# HV_PWR_STAGE_6W.net
KiCad netlist of a schematic drawn in Altium Designer
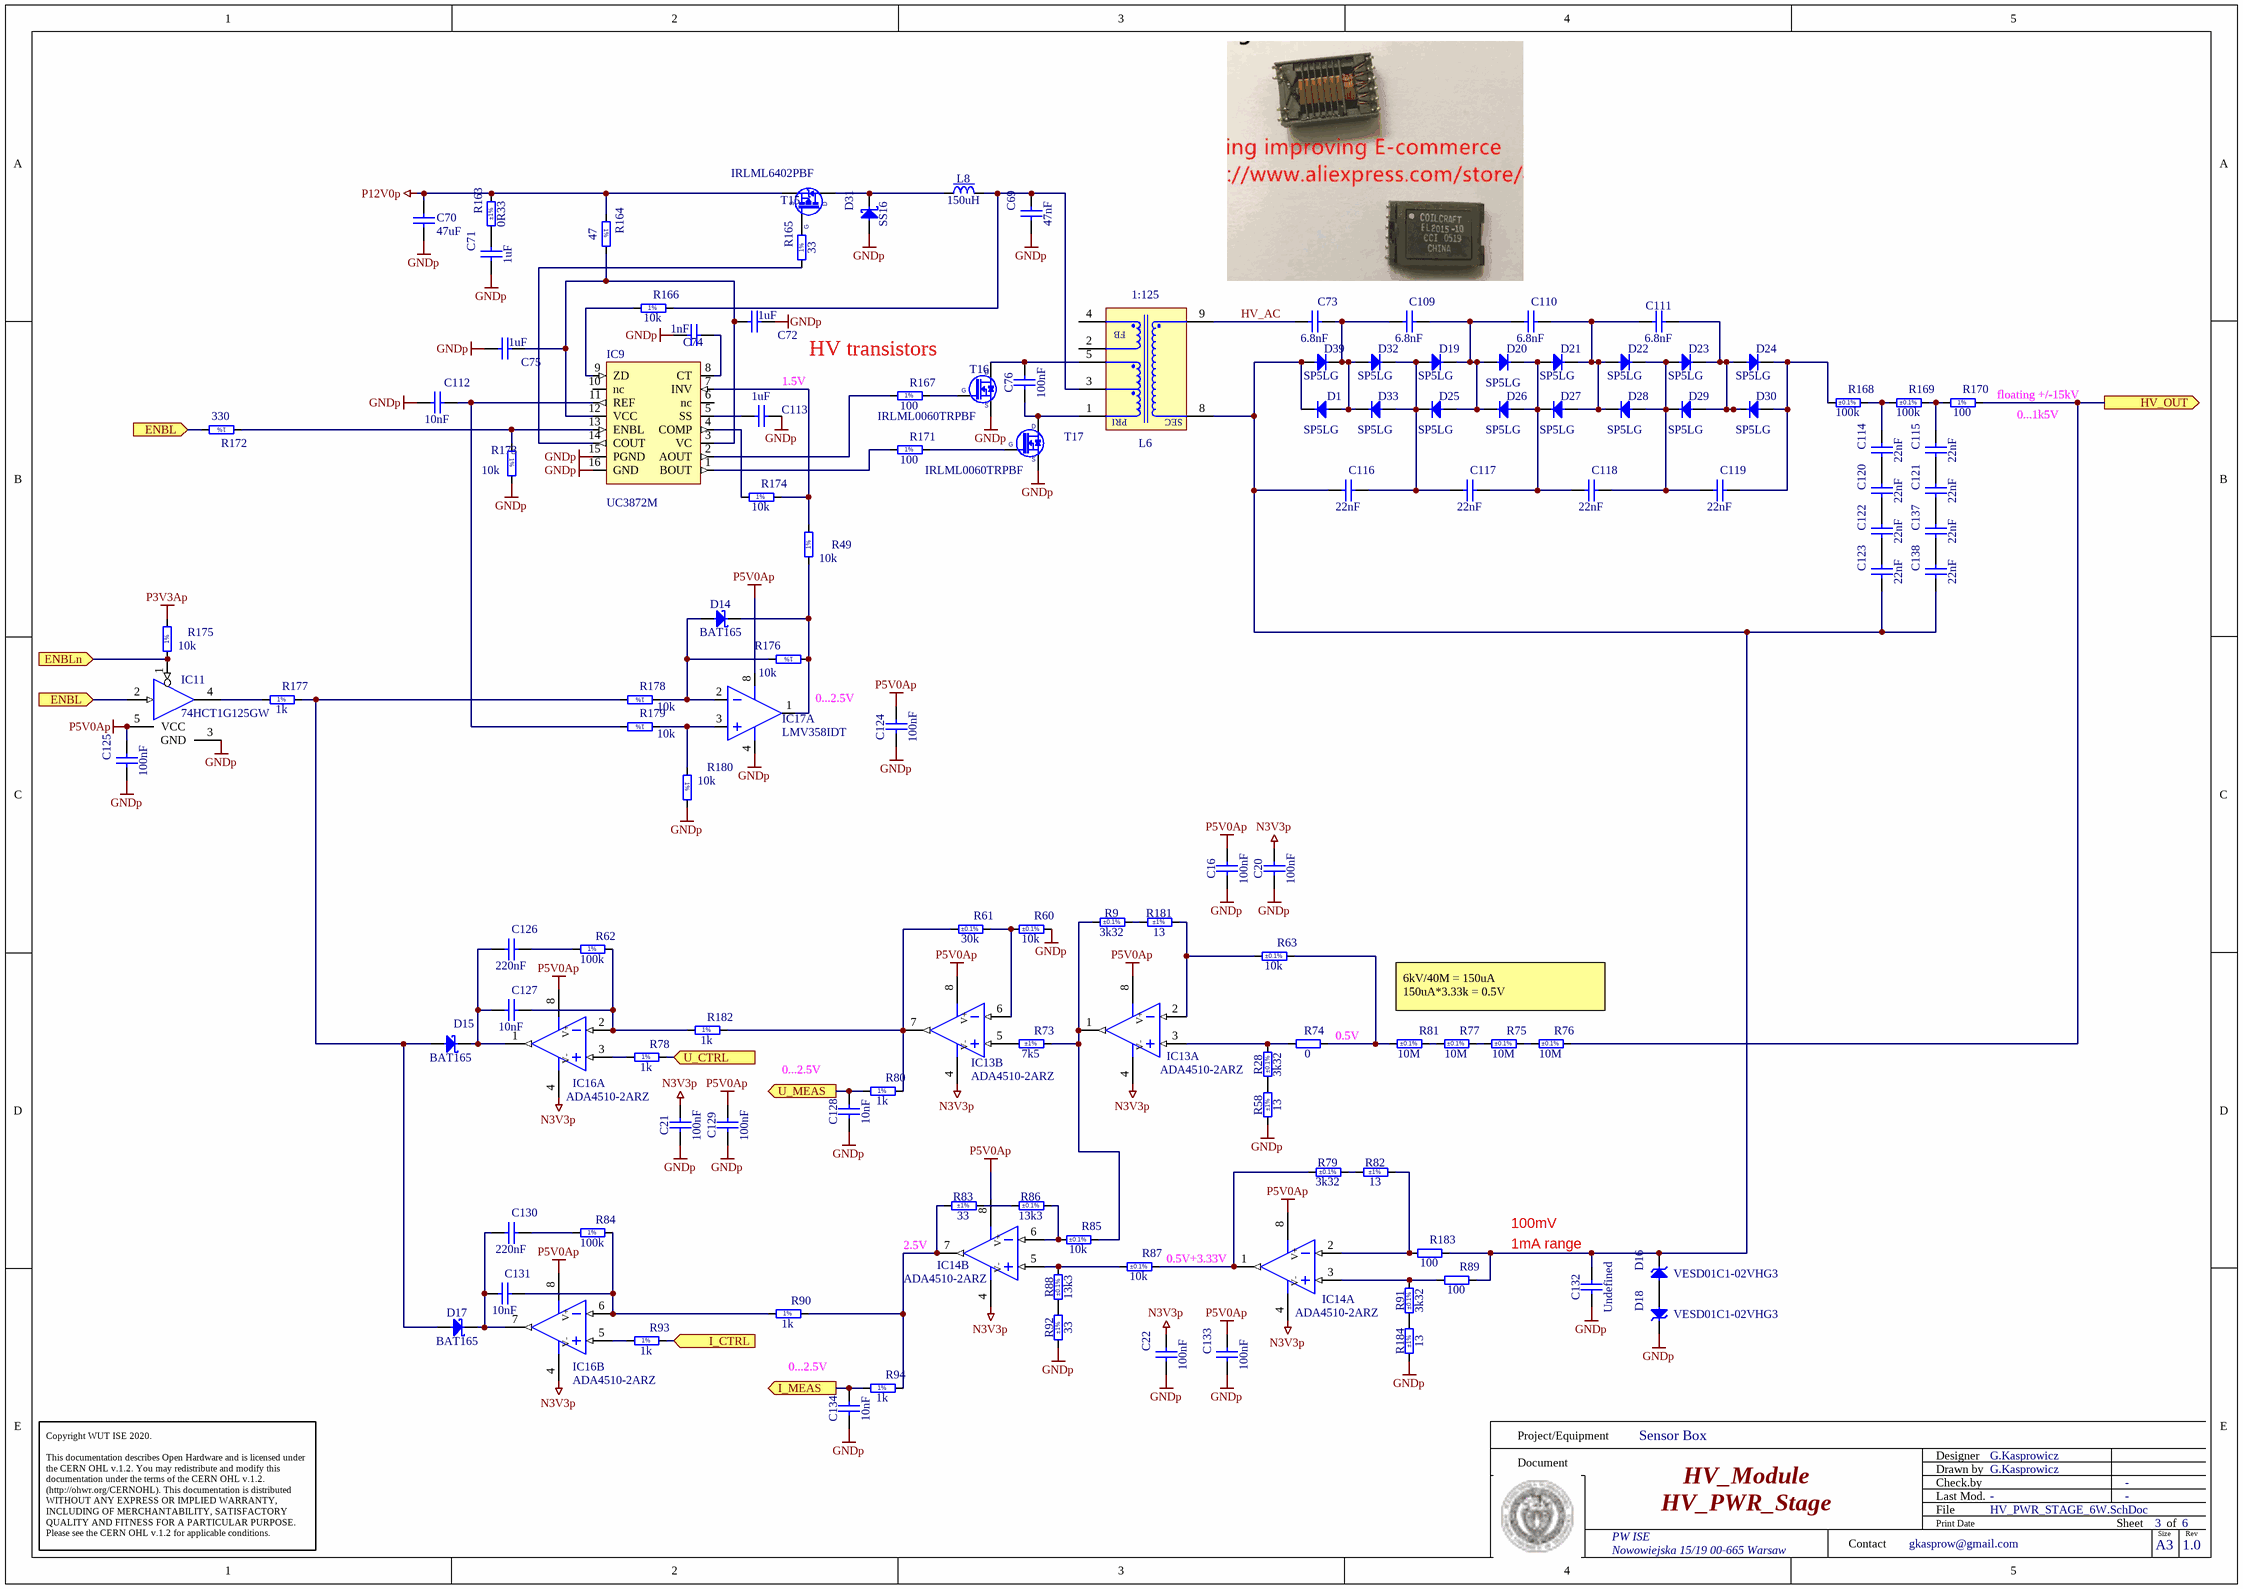
[diagram p0: HV_PWR_STAGE_6W.SchDoc]

(export (version "E")
  (design (tool "Eeschema 10.0.6"))
  (components
    (comp (ref "C16")
      (value "100nF")
      (footprint "CAPC1005X55N")
      (description "Non-polarised capacitor")
      (fields
        (field (name "PART NUMBER") "CC0402_100NF_16V_10%_X7R")
        (field (name "VOLTAGE") "16V")
        (field (name "AUTHOR") "CERN DEM JLC")
      )
      (libsource (lib "Capacitors") (part "Capacitor - non polarized"))
    )
    (comp (ref "C20")
      (value "100nF")
      (footprint "CAPC1005X55N")
      (description "Non-polarised capacitor")
      (fields
        (field (name "PART NUMBER") "CC0402_100NF_16V_10%_X7R")
        (field (name "VOLTAGE") "16V")
        (field (name "AUTHOR") "CERN DEM JLC")
      )
      (libsource (lib "Capacitors") (part "Capacitor - non polarized"))
    )
    (comp (ref "C21")
      (value "100nF")
      (footprint "CAPC1005X55N")
      (description "Non-polarised capacitor")
      (fields
        (field (name "PART NUMBER") "CC0402_100NF_16V_10%_X7R")
        (field (name "VOLTAGE") "16V")
        (field (name "AUTHOR") "CERN DEM JLC")
      )
      (libsource (lib "Capacitors") (part "Capacitor - non polarized"))
    )
    (comp (ref "C22")
      (value "100nF")
      (footprint "CAPC1005X55N")
      (description "Non-polarised capacitor")
      (fields
        (field (name "PART NUMBER") "CC0402_100NF_16V_10%_X7R")
        (field (name "VOLTAGE") "16V")
        (field (name "AUTHOR") "CERN DEM JLC")
      )
      (libsource (lib "Capacitors") (part "Capacitor - non polarized"))
    )
    (comp (ref "C69")
      (value "47nF")
      (footprint "CAPR500-250X720X650")
      (description "Non-polarised capacitor")
      (fields
        (field (name "PART NUMBER") "CPER_47NF_63V_10%_500-250X720X650")
        (field (name "VOLTAGE") "63VDC/40VAC")
        (field (name "AUTHOR") "CERN DEM JLC")
      )
      (libsource (lib "Capacitors") (part "Capacitor - non polarized"))
    )
    (comp (ref "C70")
      (value "47uF")
      (footprint "CAPC3216X180N")
      (description "Non-polarised capacitor")
      (fields
        (field (name "PART NUMBER") "CC1206_47UF_25V_20%_X5R")
        (field (name "VOLTAGE") "25V")
        (field (name "AUTHOR") "CERN DEM JLC")
      )
      (libsource (lib "Capacitors") (part "Capacitor - non polarized"))
    )
    (comp (ref "C71")
      (value "1uF")
      (footprint "CAPC1608X87N")
      (description "Non-polarised capacitor")
      (fields
        (field (name "PART NUMBER") "CC0603_1UF_25V_10%_X7R")
        (field (name "VOLTAGE") "25V")
        (field (name "AUTHOR") "CERN DEM JLC")
      )
      (libsource (lib "Capacitors") (part "Capacitor - non polarized"))
    )
    (comp (ref "C72")
      (value "1uF")
      (footprint "CAPC1608X87N")
      (description "Non-polarised capacitor")
      (fields
        (field (name "PART NUMBER") "CC0603_1UF_25V_10%_X7R")
        (field (name "VOLTAGE") "25V")
        (field (name "AUTHOR") "CERN DEM JLC")
      )
      (libsource (lib "Capacitors") (part "Capacitor - non polarized"))
    )
    (comp (ref "C73")
      (value "6.8nF")
      (footprint "CAPC3225X170N")
      (description "Non-polarised capacitor")
      (fields
        (field (name "PART NUMBER") "CC1210_6.8NF_2KV_10%_X7R")
        (field (name "VOLTAGE") "2kV")
        (field (name "AUTHOR") "GK")
      )
      (libsource (lib "Passives_RC") (part "CC1210_6.8NF_2KV_10%_X7R"))
    )
    (comp (ref "C74")
      (value "1nF")
      (footprint "CAPC1005X55N")
      (description "Non-polarised capacitor")
      (fields
        (field (name "PART NUMBER") "CC0402_1NF_50V_10%_X7R")
        (field (name "VOLTAGE") "50V")
        (field (name "AUTHOR") "CERN DEM JLC")
      )
      (libsource (lib "Capacitors") (part "Capacitor - non polarized"))
    )
    (comp (ref "C75")
      (value "1uF")
      (footprint "CAPC1608X87N")
      (description "Non-polarised capacitor")
      (fields
        (field (name "PART NUMBER") "CC0603_1UF_25V_10%_X7R")
        (field (name "VOLTAGE") "25V")
        (field (name "AUTHOR") "CERN DEM JLC")
      )
      (libsource (lib "Capacitors") (part "Capacitor - non polarized"))
    )
    (comp (ref "C76")
      (value "100nF")
      (footprint "CAPR500-250X720X650")
      (description "Non-polarised capacitor")
      (fields
        (field (name "PART NUMBER") "CPER_100NF_100V_10%_500-250X720X650")
        (field (name "VOLTAGE") "100VDC/63VAC")
        (field (name "AUTHOR") "CERN DEM JLC")
      )
      (libsource (lib "Capacitors") (part "Capacitor - non polarized"))
    )
    (comp (ref "C109")
      (value "6.8nF")
      (footprint "CAPC3225X170N")
      (description "Non-polarised capacitor")
      (fields
        (field (name "PART NUMBER") "CC1210_6.8NF_2KV_10%_X7R")
        (field (name "VOLTAGE") "2kV")
        (field (name "AUTHOR") "GK")
      )
      (libsource (lib "Passives_RC") (part "CC1210_6.8NF_2KV_10%_X7R"))
    )
    (comp (ref "C110")
      (value "6.8nF")
      (footprint "CAPC3225X170N")
      (description "Non-polarised capacitor")
      (fields
        (field (name "PART NUMBER") "CC1210_6.8NF_2KV_10%_X7R")
        (field (name "VOLTAGE") "2kV")
        (field (name "AUTHOR") "GK")
      )
      (libsource (lib "Passives_RC") (part "CC1210_6.8NF_2KV_10%_X7R"))
    )
    (comp (ref "C111")
      (value "6.8nF")
      (footprint "CAPC3225X170N")
      (description "Non-polarised capacitor")
      (fields
        (field (name "PART NUMBER") "CC1210_6.8NF_2KV_10%_X7R")
        (field (name "VOLTAGE") "2kV")
        (field (name "AUTHOR") "GK")
      )
      (libsource (lib "Passives_RC") (part "CC1210_6.8NF_2KV_10%_X7R"))
    )
    (comp (ref "C112")
      (value "10nF")
      (footprint "CAPC1608X87N")
      (description "Non-polarised capacitor")
      (fields
        (field (name "PART NUMBER") "CC0603_10NF_50V_5%_C0G")
        (field (name "VOLTAGE") "50V")
        (field (name "AUTHOR") "CERN DEM JLC")
      )
      (libsource (lib "Capacitors") (part "Capacitor - non polarized"))
    )
    (comp (ref "C113")
      (value "1uF")
      (footprint "CAPC1608X87N")
      (description "Non-polarised capacitor")
      (fields
        (field (name "PART NUMBER") "CC0603_1UF_25V_10%_X7R")
        (field (name "VOLTAGE") "25V")
        (field (name "AUTHOR") "CERN DEM JLC")
      )
      (libsource (lib "Capacitors") (part "Capacitor - non polarized"))
    )
    (comp (ref "C114")
      (value "22nF")
      (footprint "CAPC5750X330N")
      (description "Non-polarised capacitor")
      (fields
        (field (name "PART NUMBER") "CC2220_22NF_2KV_10%_X7R")
        (field (name "VOLTAGE") "2KV")
        (field (name "AUTHOR") "GK")
      )
      (libsource (lib "Passives_RC") (part "CC2220_22NF_2KV_10%_X7R"))
    )
    (comp (ref "C115")
      (value "22nF")
      (footprint "CAPC5750X330N")
      (description "Non-polarised capacitor")
      (fields
        (field (name "PART NUMBER") "CC2220_22NF_2KV_10%_X7R")
        (field (name "VOLTAGE") "2KV")
        (field (name "AUTHOR") "GK")
      )
      (libsource (lib "Passives_RC") (part "CC2220_22NF_2KV_10%_X7R"))
    )
    (comp (ref "C116")
      (value "22nF")
      (footprint "CAPC5750X330N")
      (description "Non-polarised capacitor")
      (fields
        (field (name "PART NUMBER") "CC2220_22NF_2KV_10%_X7R")
        (field (name "VOLTAGE") "2KV")
        (field (name "AUTHOR") "GK")
      )
      (libsource (lib "Passives_RC") (part "CC2220_22NF_2KV_10%_X7R"))
    )
    (comp (ref "C117")
      (value "22nF")
      (footprint "CAPC5750X330N")
      (description "Non-polarised capacitor")
      (fields
        (field (name "PART NUMBER") "CC2220_22NF_2KV_10%_X7R")
        (field (name "VOLTAGE") "2KV")
        (field (name "AUTHOR") "GK")
      )
      (libsource (lib "Passives_RC") (part "CC2220_22NF_2KV_10%_X7R"))
    )
    (comp (ref "C118")
      (value "22nF")
      (footprint "CAPC5750X330N")
      (description "Non-polarised capacitor")
      (fields
        (field (name "PART NUMBER") "CC2220_22NF_2KV_10%_X7R")
        (field (name "VOLTAGE") "2KV")
        (field (name "AUTHOR") "GK")
      )
      (libsource (lib "Passives_RC") (part "CC2220_22NF_2KV_10%_X7R"))
    )
    (comp (ref "C119")
      (value "22nF")
      (footprint "CAPC5750X330N")
      (description "Non-polarised capacitor")
      (fields
        (field (name "PART NUMBER") "CC2220_22NF_2KV_10%_X7R")
        (field (name "VOLTAGE") "2KV")
        (field (name "AUTHOR") "GK")
      )
      (libsource (lib "Passives_RC") (part "CC2220_22NF_2KV_10%_X7R"))
    )
    (comp (ref "C120")
      (value "22nF")
      (footprint "CAPC5750X330N")
      (description "Non-polarised capacitor")
      (fields
        (field (name "PART NUMBER") "CC2220_22NF_2KV_10%_X7R")
        (field (name "VOLTAGE") "2KV")
        (field (name "AUTHOR") "GK")
      )
      (libsource (lib "Passives_RC") (part "CC2220_22NF_2KV_10%_X7R"))
    )
    (comp (ref "C121")
      (value "22nF")
      (footprint "CAPC5750X330N")
      (description "Non-polarised capacitor")
      (fields
        (field (name "PART NUMBER") "CC2220_22NF_2KV_10%_X7R")
        (field (name "VOLTAGE") "2KV")
        (field (name "AUTHOR") "GK")
      )
      (libsource (lib "Passives_RC") (part "CC2220_22NF_2KV_10%_X7R"))
    )
    (comp (ref "C122")
      (value "22nF")
      (footprint "CAPC5750X330N")
      (description "Non-polarised capacitor")
      (fields
        (field (name "PART NUMBER") "CC2220_22NF_2KV_10%_X7R")
        (field (name "VOLTAGE") "2KV")
        (field (name "AUTHOR") "GK")
      )
      (libsource (lib "Passives_RC") (part "CC2220_22NF_2KV_10%_X7R"))
    )
    (comp (ref "C123")
      (value "22nF")
      (footprint "CAPC5750X330N")
      (description "Non-polarised capacitor")
      (fields
        (field (name "PART NUMBER") "CC2220_22NF_2KV_10%_X7R")
        (field (name "VOLTAGE") "2KV")
        (field (name "AUTHOR") "GK")
      )
      (libsource (lib "Passives_RC") (part "CC2220_22NF_2KV_10%_X7R"))
    )
    (comp (ref "C124")
      (value "100nF")
      (footprint "CAPC1005X55N")
      (description "Non-polarised capacitor")
      (fields
        (field (name "PART NUMBER") "CC0402_100NF_16V_10%_X7R")
        (field (name "VOLTAGE") "16V")
        (field (name "AUTHOR") "CERN DEM JLC")
      )
      (libsource (lib "Capacitors") (part "Capacitor - non polarized"))
    )
    (comp (ref "C125")
      (value "100nF")
      (footprint "CAPC1005X55N")
      (description "Non-polarised capacitor")
      (fields
        (field (name "PART NUMBER") "CC0402_100NF_16V_10%_X7R")
        (field (name "VOLTAGE") "16V")
        (field (name "AUTHOR") "CERN DEM JLC")
      )
      (libsource (lib "Capacitors") (part "Capacitor - non polarized"))
    )
    (comp (ref "C126")
      (value "220nF")
      (footprint "CAPC1608X87N")
      (description "Non-polarised capacitor")
      (fields
        (field (name "PART NUMBER") "CC0603_220NF_10V_10%_X7R")
        (field (name "VOLTAGE") "10V")
        (field (name "AUTHOR") "CERN DEM JLC")
      )
      (libsource (lib "Capacitors") (part "Capacitor - non polarized"))
    )
    (comp (ref "C127")
      (value "10nF")
      (footprint "CAPC1608X87N")
      (description "Non-polarised capacitor")
      (fields
        (field (name "PART NUMBER") "CC0603_10NF_50V_5%_C0G")
        (field (name "VOLTAGE") "50V")
        (field (name "AUTHOR") "CERN DEM JLC")
      )
      (libsource (lib "Capacitors") (part "Capacitor - non polarized"))
    )
    (comp (ref "C128")
      (value "10nF")
      (footprint "CAPC1005X55N")
      (description "Non-polarised capacitor")
      (fields
        (field (name "PART NUMBER") "CC0402_10NF_25V_10%_X7R")
        (field (name "VOLTAGE") "25V")
        (field (name "AUTHOR") "CERN DEM JLC")
      )
      (libsource (lib "Capacitors") (part "Capacitor - non polarized"))
    )
    (comp (ref "C129")
      (value "100nF")
      (footprint "CAPC1005X55N")
      (description "Non-polarised capacitor")
      (fields
        (field (name "PART NUMBER") "CC0402_100NF_16V_10%_X7R")
        (field (name "VOLTAGE") "16V")
        (field (name "AUTHOR") "CERN DEM JLC")
      )
      (libsource (lib "Capacitors") (part "Capacitor - non polarized"))
    )
    (comp (ref "C130")
      (value "220nF")
      (footprint "CAPC1608X87N")
      (description "Non-polarised capacitor")
      (fields
        (field (name "PART NUMBER") "CC0603_220NF_10V_10%_X7R")
        (field (name "VOLTAGE") "10V")
        (field (name "AUTHOR") "CERN DEM JLC")
      )
      (libsource (lib "Capacitors") (part "Capacitor - non polarized"))
    )
    (comp (ref "C131")
      (value "10nF")
      (footprint "CAPC1608X87N")
      (description "Non-polarised capacitor")
      (fields
        (field (name "PART NUMBER") "CC0603_10NF_50V_5%_C0G")
        (field (name "VOLTAGE") "50V")
        (field (name "AUTHOR") "CERN DEM JLC")
      )
      (libsource (lib "Capacitors") (part "Capacitor - non polarized"))
    )
    (comp (ref "C132")
      (value "Undefined")
      (footprint "CAPC1608X90N")
      (description "Non-polarised capacitor")
      (fields (field (name "PART NUMBER") "CC0603_NO-VALUE") (field (name "AUTHOR") "CERN DEM MR"))
      (libsource (lib "Capacitors") (part "Capacitor - non polarized"))
    )
    (comp (ref "C133")
      (value "100nF")
      (footprint "CAPC1005X55N")
      (description "Non-polarised capacitor")
      (fields
        (field (name "PART NUMBER") "CC0402_100NF_16V_10%_X7R")
        (field (name "VOLTAGE") "16V")
        (field (name "AUTHOR") "CERN DEM JLC")
      )
      (libsource (lib "Capacitors") (part "Capacitor - non polarized"))
    )
    (comp (ref "C134")
      (value "10nF")
      (footprint "CAPC1005X55N")
      (description "Non-polarised capacitor")
      (fields
        (field (name "PART NUMBER") "CC0402_10NF_25V_10%_X7R")
        (field (name "VOLTAGE") "25V")
        (field (name "AUTHOR") "CERN DEM JLC")
      )
      (libsource (lib "Capacitors") (part "Capacitor - non polarized"))
    )
    (comp (ref "C137")
      (value "22nF")
      (footprint "CAPC5750X330N")
      (description "Non-polarised capacitor")
      (fields
        (field (name "PART NUMBER") "CC2220_22NF_2KV_10%_X7R")
        (field (name "VOLTAGE") "2KV")
        (field (name "AUTHOR") "GK")
      )
      (libsource (lib "Passives_RC") (part "CC2220_22NF_2KV_10%_X7R"))
    )
    (comp (ref "C138")
      (value "22nF")
      (footprint "CAPC5750X330N")
      (description "Non-polarised capacitor")
      (fields
        (field (name "PART NUMBER") "CC2220_22NF_2KV_10%_X7R")
        (field (name "VOLTAGE") "2KV")
        (field (name "AUTHOR") "GK")
      )
      (libsource (lib "Passives_RC") (part "CC2220_22NF_2KV_10%_X7R"))
    )
    (comp (ref "D1")
      (value "SP5LG")
      (footprint "DO-214AC_GW")
      (description "270mA High Voltage Fast Recovery Rectifier 5000 Volts")
      (fields (field (name "VOLTAGE") "5000V") (field (name "POWER") "270mA") (field (name "AUTHOR") "GK"))
      (libsource (lib "Diodes") (part "D_SP5LG"))
    )
    (comp (ref "D14")
      (value "BAT165")
      (footprint "SOD2512X110N")
      (description "Schottky Diode")
      (fields
        (field (name "VOLTAGE") "40V")
        (field (name "POWER") "750mA")
        (field (name "AUTHOR") "CERN DEM JLC")
      )
      (libsource (lib "ICs And Semiconductors") (part "Diode Schottky"))
    )
    (comp (ref "D15")
      (value "BAT165")
      (footprint "SOD2512X110N")
      (description "Schottky Diode")
      (fields
        (field (name "VOLTAGE") "40V")
        (field (name "POWER") "750mA")
        (field (name "AUTHOR") "CERN DEM JLC")
      )
      (libsource (lib "ICs And Semiconductors") (part "Diode Schottky"))
    )
    (comp (ref "D16")
      (value "VESD01C1-02VHG3")
      (footprint "SODFL1608X70N")
      (description "Transient Voltage Suppressor Diode (Uni-Directional)")
      (fields
        (field (name "VOLTAGE") "1V")
        (field (name "POWER") "100W")
        (field (name "AUTHOR") "CERN DEM BC")
      )
      (libsource (lib "ICs And Semiconductors") (part "Diode TVS Uni-Directional"))
    )
    (comp (ref "D17")
      (value "BAT165")
      (footprint "SOD2512X110N")
      (description "Schottky Diode")
      (fields
        (field (name "VOLTAGE") "40V")
        (field (name "POWER") "750mA")
        (field (name "AUTHOR") "CERN DEM JLC")
      )
      (libsource (lib "ICs And Semiconductors") (part "Diode Schottky"))
    )
    (comp (ref "D18")
      (value "VESD01C1-02VHG3")
      (footprint "SODFL1608X70N")
      (description "Transient Voltage Suppressor Diode (Uni-Directional)")
      (fields
        (field (name "VOLTAGE") "1V")
        (field (name "POWER") "100W")
        (field (name "AUTHOR") "CERN DEM BC")
      )
      (libsource (lib "ICs And Semiconductors") (part "Diode TVS Uni-Directional"))
    )
    (comp (ref "D19")
      (value "SP5LG")
      (footprint "DO-214AC_GW")
      (description "270mA High Voltage Fast Recovery Rectifier 5000 Volts")
      (fields (field (name "VOLTAGE") "5000V") (field (name "POWER") "270mA") (field (name "AUTHOR") "GK"))
      (libsource (lib "Diodes") (part "D_SP5LG"))
    )
    (comp (ref "D20")
      (value "SP5LG")
      (footprint "DO-214AC_GW")
      (description "270mA High Voltage Fast Recovery Rectifier 5000 Volts")
      (fields (field (name "VOLTAGE") "5000V") (field (name "POWER") "270mA") (field (name "AUTHOR") "GK"))
      (libsource (lib "Diodes") (part "D_SP5LG"))
    )
    (comp (ref "D21")
      (value "SP5LG")
      (footprint "DO-214AC_GW")
      (description "270mA High Voltage Fast Recovery Rectifier 5000 Volts")
      (fields (field (name "VOLTAGE") "5000V") (field (name "POWER") "270mA") (field (name "AUTHOR") "GK"))
      (libsource (lib "Diodes") (part "D_SP5LG"))
    )
    (comp (ref "D22")
      (value "SP5LG")
      (footprint "DO-214AC_GW")
      (description "270mA High Voltage Fast Recovery Rectifier 5000 Volts")
      (fields (field (name "VOLTAGE") "5000V") (field (name "POWER") "270mA") (field (name "AUTHOR") "GK"))
      (libsource (lib "Diodes") (part "D_SP5LG"))
    )
    (comp (ref "D23")
      (value "SP5LG")
      (footprint "DO-214AC_GW")
      (description "270mA High Voltage Fast Recovery Rectifier 5000 Volts")
      (fields (field (name "VOLTAGE") "5000V") (field (name "POWER") "270mA") (field (name "AUTHOR") "GK"))
      (libsource (lib "Diodes") (part "D_SP5LG"))
    )
    (comp (ref "D24")
      (value "SP5LG")
      (footprint "DO-214AC_GW")
      (description "270mA High Voltage Fast Recovery Rectifier 5000 Volts")
      (fields (field (name "VOLTAGE") "5000V") (field (name "POWER") "270mA") (field (name "AUTHOR") "GK"))
      (libsource (lib "Diodes") (part "D_SP5LG"))
    )
    (comp (ref "D25")
      (value "SP5LG")
      (footprint "DO-214AC_GW")
      (description "270mA High Voltage Fast Recovery Rectifier 5000 Volts")
      (fields (field (name "VOLTAGE") "5000V") (field (name "POWER") "270mA") (field (name "AUTHOR") "GK"))
      (libsource (lib "Diodes") (part "D_SP5LG"))
    )
    (comp (ref "D26")
      (value "SP5LG")
      (footprint "DO-214AC_GW")
      (description "270mA High Voltage Fast Recovery Rectifier 5000 Volts")
      (fields (field (name "VOLTAGE") "5000V") (field (name "POWER") "270mA") (field (name "AUTHOR") "GK"))
      (libsource (lib "Diodes") (part "D_SP5LG"))
    )
    (comp (ref "D27")
      (value "SP5LG")
      (footprint "DO-214AC_GW")
      (description "270mA High Voltage Fast Recovery Rectifier 5000 Volts")
      (fields (field (name "VOLTAGE") "5000V") (field (name "POWER") "270mA") (field (name "AUTHOR") "GK"))
      (libsource (lib "Diodes") (part "D_SP5LG"))
    )
    (comp (ref "D28")
      (value "SP5LG")
      (footprint "DO-214AC_GW")
      (description "270mA High Voltage Fast Recovery Rectifier 5000 Volts")
      (fields (field (name "VOLTAGE") "5000V") (field (name "POWER") "270mA") (field (name "AUTHOR") "GK"))
      (libsource (lib "Diodes") (part "D_SP5LG"))
    )
    (comp (ref "D29")
      (value "SP5LG")
      (footprint "DO-214AC_GW")
      (description "270mA High Voltage Fast Recovery Rectifier 5000 Volts")
      (fields (field (name "VOLTAGE") "5000V") (field (name "POWER") "270mA") (field (name "AUTHOR") "GK"))
      (libsource (lib "Diodes") (part "D_SP5LG"))
    )
    (comp (ref "D30")
      (value "SP5LG")
      (footprint "DO-214AC_GW")
      (description "270mA High Voltage Fast Recovery Rectifier 5000 Volts")
      (fields (field (name "VOLTAGE") "5000V") (field (name "POWER") "270mA") (field (name "AUTHOR") "GK"))
      (libsource (lib "Diodes") (part "D_SP5LG"))
    )
    (comp (ref "D31")
      (value "SS16")
      (footprint "DIOM5127X229N")
      (description "Schottky Diode")
      (fields
        (field (name "VOLTAGE") "60V")
        (field (name "POWER") "1A")
        (field (name "AUTHOR") "CERN DEM JLC")
      )
      (libsource (lib "ICs And Semiconductors") (part "Diode Schottky"))
    )
    (comp (ref "D32")
      (value "SP5LG")
      (footprint "DO-214AC_GW")
      (description "270mA High Voltage Fast Recovery Rectifier 5000 Volts")
      (fields (field (name "VOLTAGE") "5000V") (field (name "POWER") "270mA") (field (name "AUTHOR") "GK"))
      (libsource (lib "Diodes") (part "D_SP5LG"))
    )
    (comp (ref "D33")
      (value "SP5LG")
      (footprint "DO-214AC_GW")
      (description "270mA High Voltage Fast Recovery Rectifier 5000 Volts")
      (fields (field (name "VOLTAGE") "5000V") (field (name "POWER") "270mA") (field (name "AUTHOR") "GK"))
      (libsource (lib "Diodes") (part "D_SP5LG"))
    )
    (comp (ref "D39")
      (value "SP5LG")
      (footprint "DO-214AC_GW")
      (description "270mA High Voltage Fast Recovery Rectifier 5000 Volts")
      (fields (field (name "VOLTAGE") "5000V") (field (name "POWER") "270mA") (field (name "AUTHOR") "GK"))
      (libsource (lib "Diodes") (part "D_SP5LG"))
    )
    (comp (ref "IC9")
      (value "UC3872M")
      (footprint "R-PDSO-G16")
      (description "Resonant Lamp Ballast Controller")
      (libsource (lib "LIBRARY_SCH") (part "UC3872"))
    )
    (comp (ref "IC11")
      (value "74HCT1G125GW")
      (footprint "SOT65P210X110-5N")
      (description "Single Bus Buffer Gate With 3-State Output")
      (fields (field (name "MANUFACTURER") "NEXPERIA") (field (name "AUTHOR") "CERN DEM JMW"))
      (libsource (lib "ICs And Semiconductors") (part "741G125"))
    )
    (comp (ref "IC13")
      (value "ADA4510-2ARZ")
      (footprint "SOIC127P600X175-8N")
      (description "Precision, 40 V, ±70 nV/°C, Rail-to-Rail Input and Output Op Amp with DigiTrim")
      (fields (field (name "MANUFACTURER") "ANALOG DEVICES") (field (name "AUTHOR") "GK"))
      (libsource (lib "Amplifiers") (part "OA_ADA4510-2ARZ"))
    )
    (comp (ref "IC14")
      (value "ADA4510-2ARZ")
      (footprint "SOIC127P600X175-8N")
      (description "Precision, 40 V, ±70 nV/°C, Rail-to-Rail Input and Output Op Amp with DigiTrim")
      (fields (field (name "MANUFACTURER") "ANALOG DEVICES") (field (name "AUTHOR") "GK"))
      (libsource (lib "Amplifiers") (part "OA_ADA4510-2ARZ"))
    )
    (comp (ref "IC16")
      (value "ADA4510-2ARZ")
      (footprint "SOIC127P600X175-8N")
      (description "Precision, 40 V, ±70 nV/°C, Rail-to-Rail Input and Output Op Amp with DigiTrim")
      (fields (field (name "MANUFACTURER") "ANALOG DEVICES") (field (name "AUTHOR") "GK"))
      (libsource (lib "Amplifiers") (part "OA_ADA4510-2ARZ"))
    )
    (comp (ref "IC17")
      (value "LMV358IDT")
      (footprint "SO-8")
      (description "Low voltage, Rail-to_Rail output Operational Amplifier")
      (libsource (lib "Amplifiers") (part "OA_LMV358"))
    )
    (comp (ref "L6")
      (value "1:125")
      (footprint "XFMR_COILCRAFT_FL0215_PACK1")
      (description "Shielded Power Inductor")
      (fields
        (field (name "PART NUMBER") "XFMR_COILCRAFT_FL2015-5L")
        (field (name "MANUFACTURER") "COILCRAFT")
        (field (name "AUTHOR") "CERN DEM HF")
      )
      (libsource (lib "Inductors & Transformers") (part "XFMR_COILCRAFT_FL2015_A"))
    )
    (comp (ref "L8")
      (value "150uH")
      (footprint "IND_WURTH_WE-TPC_1038")
      (description "Inductor With Core")
      (fields
        (field (name "PART NUMBER") "IND_150UH_30%_WURTH_WE-TPC_744066151")
        (field (name "POWER") "3A")
        (field (name "AUTHOR") "CERN DEM HF")
      )
      (libsource (lib "Inductors & Transformers") (part "Inductor With Magnetic core"))
    )
    (comp (ref "R9")
      (value "3k32")
      (footprint "RESC1608X55N")
      (description "Resistor - 0.1%")
      (fields
        (field (name "TOLERANCE") "±0.1%")
        (field (name "PART NUMBER") "R0603_3K32_0.1%_0.063W_10PPM")
        (field (name "POWER") "0.063W")
        (field (name "AUTHOR") "CERN DEM JLC")
      )
      (libsource (lib "Resistors") (part "Resistor - 0.1%"))
    )
    (comp (ref "R28")
      (value "3k32")
      (footprint "RESC1608X55N")
      (description "Resistor - 0.1%")
      (fields
        (field (name "TOLERANCE") "±0.1%")
        (field (name "PART NUMBER") "R0603_3K32_0.1%_0.063W_10PPM")
        (field (name "POWER") "0.063W")
        (field (name "AUTHOR") "CERN DEM JLC")
      )
      (libsource (lib "Resistors") (part "Resistor - 0.1%"))
    )
    (comp (ref "R49")
      (value "10k")
      (footprint "RESC1005X40N")
      (description "Resistor - 1%")
      (fields
        (field (name "PART NUMBER") "R0402_10K_1%_0.0625W_100PPM")
        (field (name "POWER") "0.0625W")
        (field (name "AUTHOR") "CERN DEM JLC")
      )
      (libsource (lib "") (part "Resistor - 1%_1"))
    )
    (comp (ref "R58")
      (value "13")
      (footprint "RESC1005X40N")
      (description "Resistor - 1%")
      (fields
        (field (name "TOLERANCE") "±1%")
        (field (name "PART NUMBER") "R0402_13R_1%_0.0625W_100PPM")
        (field (name "POWER") "0.0625W")
        (field (name "AUTHOR") "CERN DEM JLC")
      )
      (libsource (lib "") (part "Resistor - 1%_1"))
    )
    (comp (ref "R60")
      (value "10k")
      (footprint "RESC1608X55N")
      (description "Resistor - 0.1%")
      (fields
        (field (name "TOLERANCE") "±0.1%")
        (field (name "PART NUMBER") "R0603_10K_0.1%_0.063W_10PPM")
        (field (name "POWER") "0.063W")
        (field (name "AUTHOR") "CERN DEM JLC")
      )
      (libsource (lib "Resistors") (part "Resistor - 0.1%"))
    )
    (comp (ref "R61")
      (value "30k")
      (footprint "RESC1608X55N")
      (description "Resistor - 0.1%")
      (fields
        (field (name "TOLERANCE") "±0.1%")
        (field (name "PART NUMBER") "R0603_30K_0.1%_0.063W_25PPM")
        (field (name "POWER") "0.063W")
        (field (name "AUTHOR") "CERN DEM JMW")
      )
      (libsource (lib "Resistors") (part "Resistor - 0.1%"))
    )
    (comp (ref "R62")
      (value "100k")
      (footprint "RESC1608X55N")
      (description "Resistor - 1%")
      (fields
        (field (name "PART NUMBER") "R0603_100K_1%_0.1W_100PPM")
        (field (name "POWER") "0.1W")
        (field (name "AUTHOR") "CERN DEM JLC")
      )
      (libsource (lib "") (part "Resistor - 1%_1"))
    )
    (comp (ref "R63")
      (value "10k")
      (footprint "RESC1608X55N")
      (description "Resistor - 0.1%")
      (fields
        (field (name "TOLERANCE") "±0.1%")
        (field (name "PART NUMBER") "R0603_10K_0.1%_0.063W_10PPM")
        (field (name "POWER") "0.063W")
        (field (name "AUTHOR") "CERN DEM JLC")
      )
      (libsource (lib "Resistors") (part "Resistor - 0.1%"))
    )
    (comp (ref "R73")
      (value "7k5")
      (footprint "RESC1608X55N")
      (description "Resistor - 1%")
      (fields
        (field (name "TOLERANCE") "±1%")
        (field (name "PART NUMBER") "R0603_7K5_1%_0.1W_100PPM")
        (field (name "POWER") "0.1W")
        (field (name "AUTHOR") "CERN DEM JLC")
      )
      (libsource (lib "Resistors") (part "Resistor - 1%"))
    )
    (comp (ref "R74")
      (value "0")
      (footprint "RESC1005X40N")
      (description "Resistor")
      (fields
        (field (name "PART NUMBER") "R0402_0R_JUMPER")
        (field (name "MANUFACTURER") "GENERIC")
        (field (name "AUTHOR") "CERN DEM JLC")
      )
      (libsource (lib "Resistors") (part "Resistor"))
    )
    (comp (ref "R75")
      (value "10M")
      (footprint "RESC5025X65N")
      (description "RES, HV, 2010, 10 Mohm, 0.1%, 25 ppm, 1W")
      (fields
        (field (name "PART NUMBER") "R1210_1M0_0.1%_1W_25ppm_HVCB2010BDE10M0")
        (field (name "POWER") "1W")
        (field (name "TOLERANCE") "±0.1%")
        (field (name "AUTHOR") "GK")
      )
      (libsource (lib "Passives_RC") (part "R1210_1M0_0.1%_1W_25ppm_HVCB2010BDE10M0"))
    )
    (comp (ref "R76")
      (value "10M")
      (footprint "RESC5025X65N")
      (description "RES, HV, 2010, 10 Mohm, 0.1%, 25 ppm, 1W")
      (fields
        (field (name "PART NUMBER") "R1210_1M0_0.1%_1W_25ppm_HVCB2010BDE10M0")
        (field (name "POWER") "1W")
        (field (name "TOLERANCE") "±0.1%")
        (field (name "AUTHOR") "GK")
      )
      (libsource (lib "Passives_RC") (part "R1210_1M0_0.1%_1W_25ppm_HVCB2010BDE10M0"))
    )
    (comp (ref "R77")
      (value "10M")
      (footprint "RESC5025X65N")
      (description "RES, HV, 2010, 10 Mohm, 0.1%, 25 ppm, 1W")
      (fields
        (field (name "PART NUMBER") "R1210_1M0_0.1%_1W_25ppm_HVCB2010BDE10M0")
        (field (name "POWER") "1W")
        (field (name "TOLERANCE") "±0.1%")
        (field (name "AUTHOR") "GK")
      )
      (libsource (lib "Passives_RC") (part "R1210_1M0_0.1%_1W_25ppm_HVCB2010BDE10M0"))
    )
    (comp (ref "R78")
      (value "1k")
      (footprint "RESC1005X40N")
      (description "Resistor - 1%")
      (fields
        (field (name "PART NUMBER") "R0402_1K_1%_0.0625W_100PPM")
        (field (name "POWER") "0.0625W")
        (field (name "AUTHOR") "CERN DEM JLC")
      )
      (libsource (lib "") (part "Resistor - 1%_1"))
    )
    (comp (ref "R79")
      (value "3k32")
      (footprint "RESC1608X55N")
      (description "Resistor - 0.1%")
      (fields
        (field (name "TOLERANCE") "±0.1%")
        (field (name "PART NUMBER") "R0603_3K32_0.1%_0.063W_10PPM")
        (field (name "POWER") "0.063W")
        (field (name "AUTHOR") "CERN DEM JLC")
      )
      (libsource (lib "Resistors") (part "Resistor - 0.1%"))
    )
    (comp (ref "R80")
      (value "1k")
      (footprint "RESC1005X40N")
      (description "Resistor - 1%")
      (fields
        (field (name "PART NUMBER") "R0402_1K_1%_0.0625W_100PPM")
        (field (name "POWER") "0.0625W")
        (field (name "AUTHOR") "CERN DEM JLC")
      )
      (libsource (lib "") (part "Resistor - 1%_1"))
    )
    (comp (ref "R81")
      (value "10M")
      (footprint "RESC5025X65N")
      (description "RES, HV, 2010, 10 Mohm, 0.1%, 25 ppm, 1W")
      (fields
        (field (name "PART NUMBER") "R1210_1M0_0.1%_1W_25ppm_HVCB2010BDE10M0")
        (field (name "POWER") "1W")
        (field (name "TOLERANCE") "±0.1%")
        (field (name "AUTHOR") "GK")
      )
      (libsource (lib "Passives_RC") (part "R1210_1M0_0.1%_1W_25ppm_HVCB2010BDE10M0"))
    )
    (comp (ref "R82")
      (value "13")
      (footprint "RESC1005X40N")
      (description "Resistor - 1%")
      (fields
        (field (name "TOLERANCE") "±1%")
        (field (name "PART NUMBER") "R0402_13R_1%_0.0625W_100PPM")
        (field (name "POWER") "0.0625W")
        (field (name "AUTHOR") "CERN DEM JLC")
      )
      (libsource (lib "") (part "Resistor - 1%_1"))
    )
    (comp (ref "R83")
      (value "33")
      (footprint "RESC1005X40N")
      (description "Resistor - 1%")
      (fields
        (field (name "TOLERANCE") "±1%")
        (field (name "PART NUMBER") "R0402_33R_1%_0.0625W_100PPM")
        (field (name "POWER") "0.0625W")
        (field (name "AUTHOR") "CERN DEM JLC")
      )
      (libsource (lib "") (part "Resistor - 1%_1"))
    )
    (comp (ref "R84")
      (value "100k")
      (footprint "RESC1608X55N")
      (description "Resistor - 1%")
      (fields
        (field (name "PART NUMBER") "R0603_100K_1%_0.1W_100PPM")
        (field (name "POWER") "0.1W")
        (field (name "AUTHOR") "CERN DEM JLC")
      )
      (libsource (lib "") (part "Resistor - 1%_1"))
    )
    (comp (ref "R85")
      (value "10k")
      (footprint "RESC1608X55N")
      (description "Resistor - 0.1%")
      (fields
        (field (name "TOLERANCE") "±0.1%")
        (field (name "PART NUMBER") "R0603_10K_0.1%_0.063W_10PPM")
        (field (name "POWER") "0.063W")
        (field (name "AUTHOR") "CERN DEM JLC")
      )
      (libsource (lib "Resistors") (part "Resistor - 0.1%"))
    )
    (comp (ref "R86")
      (value "13k3")
      (footprint "RESC1608X55N")
      (description "Resistor - 0.1%")
      (fields
        (field (name "TOLERANCE") "±0.1%")
        (field (name "PART NUMBER") "R0603_13K3_0.1%_0.063W_10PPM")
        (field (name "POWER") "0.063W")
        (field (name "AUTHOR") "CERN DEM JLC")
      )
      (libsource (lib "Resistors") (part "Resistor - 0.1%"))
    )
    (comp (ref "R87")
      (value "10k")
      (footprint "RESC1608X55N")
      (description "Resistor - 0.1%")
      (fields
        (field (name "TOLERANCE") "±0.1%")
        (field (name "PART NUMBER") "R0603_10K_0.1%_0.063W_10PPM")
        (field (name "POWER") "0.063W")
        (field (name "AUTHOR") "CERN DEM JLC")
      )
      (libsource (lib "Resistors") (part "Resistor - 0.1%"))
    )
    (comp (ref "R88")
      (value "13k3")
      (footprint "RESC1608X55N")
      (description "Resistor - 0.1%")
      (fields
        (field (name "TOLERANCE") "±0.1%")
        (field (name "PART NUMBER") "R0603_13K3_0.1%_0.063W_10PPM")
        (field (name "POWER") "0.063W")
        (field (name "AUTHOR") "CERN DEM JLC")
      )
      (libsource (lib "Resistors") (part "Resistor - 0.1%"))
    )
    (comp (ref "R89")
      (value "100")
      (footprint "RESC1005X40N")
      (description "Resistor - 1%")
      (fields
        (field (name "PART NUMBER") "R0402_100R_1%_0.0625W_100PPM")
        (field (name "POWER") "0.0625W")
        (field (name "AUTHOR") "CERN DEM JLC")
      )
      (libsource (lib "") (part "Resistor - 1%_1"))
    )
    (comp (ref "R90")
      (value "1k")
      (footprint "RESC1005X40N")
      (description "Resistor - 1%")
      (fields
        (field (name "PART NUMBER") "R0402_1K_1%_0.0625W_100PPM")
        (field (name "POWER") "0.0625W")
        (field (name "AUTHOR") "CERN DEM JLC")
      )
      (libsource (lib "") (part "Resistor - 1%_1"))
    )
    (comp (ref "R91")
      (value "3k32")
      (footprint "RESC1608X55N")
      (description "Resistor - 0.1%")
      (fields
        (field (name "TOLERANCE") "±0.1%")
        (field (name "PART NUMBER") "R0603_3K32_0.1%_0.063W_10PPM")
        (field (name "POWER") "0.063W")
        (field (name "AUTHOR") "CERN DEM JLC")
      )
      (libsource (lib "Resistors") (part "Resistor - 0.1%"))
    )
    (comp (ref "R92")
      (value "33")
      (footprint "RESC1005X40N")
      (description "Resistor - 1%")
      (fields
        (field (name "TOLERANCE") "±1%")
        (field (name "PART NUMBER") "R0402_33R_1%_0.0625W_100PPM")
        (field (name "POWER") "0.0625W")
        (field (name "AUTHOR") "CERN DEM JLC")
      )
      (libsource (lib "") (part "Resistor - 1%_1"))
    )
    (comp (ref "R93")
      (value "1k")
      (footprint "RESC1005X40N")
      (description "Resistor - 1%")
      (fields
        (field (name "PART NUMBER") "R0402_1K_1%_0.0625W_100PPM")
        (field (name "POWER") "0.0625W")
        (field (name "AUTHOR") "CERN DEM JLC")
      )
      (libsource (lib "") (part "Resistor - 1%_1"))
    )
    (comp (ref "R94")
      (value "1k")
      (footprint "RESC1005X40N")
      (description "Resistor - 1%")
      (fields
        (field (name "PART NUMBER") "R0402_1K_1%_0.0625W_100PPM")
        (field (name "POWER") "0.0625W")
        (field (name "AUTHOR") "CERN DEM JLC")
      )
      (libsource (lib "") (part "Resistor - 1%_1"))
    )
    (comp (ref "R163")
      (value "0R33")
      (footprint "RESC1608X60N")
      (description "Resistor - 1%")
      (fields
        (field (name "TOLERANCE") "±1%")
        (field (name "PART NUMBER") "R0603_0R33_1%_0.2W_100PPM")
        (field (name "POWER") "0.2W")
        (field (name "AUTHOR") "CERN DEM BC")
      )
      (libsource (lib "Resistors") (part "Resistor - 1%"))
    )
    (comp (ref "R164")
      (value "47")
      (footprint "RESC1608X55N")
      (description "Resistor - 1%")
      (fields
        (field (name "PART NUMBER") "R0603_47R_1%_0.1W_100PPM")
        (field (name "POWER") "0.1W")
        (field (name "AUTHOR") "CERN DEM JLC")
      )
      (libsource (lib "") (part "Resistor - 1%_1"))
    )
    (comp (ref "R165")
      (value "33")
      (footprint "RESC1005X40N")
      (description "Resistor - 1%")
      (fields
        (field (name "PART NUMBER") "R0402_33R_1%_0.0625W_100PPM")
        (field (name "POWER") "0.0625W")
        (field (name "AUTHOR") "CERN DEM JLC")
      )
      (libsource (lib "") (part "Resistor - 1%_1"))
    )
    (comp (ref "R166")
      (value "10k")
      (footprint "RESC1005X40N")
      (description "Resistor - 1%")
      (fields
        (field (name "PART NUMBER") "R0402_10K_1%_0.0625W_100PPM")
        (field (name "POWER") "0.0625W")
        (field (name "AUTHOR") "CERN DEM JLC")
      )
      (libsource (lib "") (part "Resistor - 1%_1"))
    )
    (comp (ref "R167")
      (value "100")
      (footprint "RESC1005X40N")
      (description "Resistor - 1%")
      (fields
        (field (name "PART NUMBER") "R0402_100R_1%_0.0625W_100PPM")
        (field (name "POWER") "0.0625W")
        (field (name "AUTHOR") "CERN DEM JLC")
      )
      (libsource (lib "") (part "Resistor - 1%_1"))
    )
    (comp (ref "R168")
      (value "100k")
      (footprint "RESC3216X50N")
      (description "Resistor - 0.1%")
      (fields
        (field (name "TOLERANCE") "±0.1%")
        (field (name "PART NUMBER") "R1206_100K_0.1%_0.4W_25PPM_VISHAY_PAT")
        (field (name "POWER") "0.4W")
        (field (name "AUTHOR") "CERN DEM MR")
      )
      (libsource (lib "Resistors") (part "Resistor - 0.1%"))
    )
    (comp (ref "R169")
      (value "100k")
      (footprint "RESC3216X50N")
      (description "Resistor - 0.1%")
      (fields
        (field (name "TOLERANCE") "±0.1%")
        (field (name "PART NUMBER") "R1206_100K_0.1%_0.4W_25PPM_VISHAY_PAT")
        (field (name "POWER") "0.4W")
        (field (name "AUTHOR") "CERN DEM MR")
      )
      (libsource (lib "Resistors") (part "Resistor - 0.1%"))
    )
    (comp (ref "R170")
      (value "100")
      (footprint "RESC6331X70N")
      (description "Resistor - 1%")
      (fields
        (field (name "PART NUMBER") "R2512_100R_1%_1.5W_100PPM_VISHAY_CRCW-HP e3")
        (field (name "POWER") "1.5W")
        (field (name "AUTHOR") "CERN DEM JLC")
      )
      (libsource (lib "") (part "Resistor - 1%_1"))
    )
    (comp (ref "R171")
      (value "100")
      (footprint "RESC1005X40N")
      (description "Resistor - 1%")
      (fields
        (field (name "PART NUMBER") "R0402_100R_1%_0.0625W_100PPM")
        (field (name "POWER") "0.0625W")
        (field (name "AUTHOR") "CERN DEM JLC")
      )
      (libsource (lib "") (part "Resistor - 1%_1"))
    )
    (comp (ref "R172")
      (value "330")
      (footprint "RESC1005X40N")
      (description "Resistor - 1%")
      (fields
        (field (name "PART NUMBER") "R0402_330R_1%_0.0625W_100PPM")
        (field (name "POWER") "0.0625W")
        (field (name "AUTHOR") "CERN DEM JLC")
      )
      (libsource (lib "") (part "Resistor - 1%_1"))
    )
    (comp (ref "R173")
      (value "10k")
      (footprint "RESC1005X40N")
      (description "Resistor - 1%")
      (fields
        (field (name "PART NUMBER") "R0402_10K_1%_0.0625W_100PPM")
        (field (name "POWER") "0.0625W")
        (field (name "AUTHOR") "CERN DEM JLC")
      )
      (libsource (lib "") (part "Resistor - 1%_1"))
    )
    (comp (ref "R174")
      (value "10k")
      (footprint "RESC1005X40N")
      (description "Resistor - 1%")
      (fields
        (field (name "PART NUMBER") "R0402_10K_1%_0.0625W_100PPM")
        (field (name "POWER") "0.0625W")
        (field (name "AUTHOR") "CERN DEM JLC")
      )
      (libsource (lib "") (part "Resistor - 1%_1"))
    )
    (comp (ref "R175")
      (value "10k")
      (footprint "RESC1005X40N")
      (description "Resistor - 1%")
      (fields
        (field (name "PART NUMBER") "R0402_10K_1%_0.0625W_100PPM")
        (field (name "POWER") "0.0625W")
        (field (name "AUTHOR") "CERN DEM JLC")
      )
      (libsource (lib "") (part "Resistor - 1%_1"))
    )
    (comp (ref "R176")
      (value "10k")
      (footprint "RESC1005X40N")
      (description "Resistor - 1%")
      (fields
        (field (name "PART NUMBER") "R0402_10K_1%_0.0625W_100PPM")
        (field (name "POWER") "0.0625W")
        (field (name "AUTHOR") "CERN DEM JLC")
      )
      (libsource (lib "") (part "Resistor - 1%_1"))
    )
    (comp (ref "R177")
      (value "1k")
      (footprint "RESC1005X40N")
      (description "Resistor - 1%")
      (fields
        (field (name "PART NUMBER") "R0402_1K_1%_0.0625W_100PPM")
        (field (name "POWER") "0.0625W")
        (field (name "AUTHOR") "CERN DEM JLC")
      )
      (libsource (lib "") (part "Resistor - 1%_1"))
    )
    (comp (ref "R178")
      (value "10k")
      (footprint "RESC1005X40N")
      (description "Resistor - 1%")
      (fields
        (field (name "PART NUMBER") "R0402_10K_1%_0.0625W_100PPM")
        (field (name "POWER") "0.0625W")
        (field (name "AUTHOR") "CERN DEM JLC")
      )
      (libsource (lib "") (part "Resistor - 1%_1"))
    )
    (comp (ref "R179")
      (value "10k")
      (footprint "RESC1005X40N")
      (description "Resistor - 1%")
      (fields
        (field (name "PART NUMBER") "R0402_10K_1%_0.0625W_100PPM")
        (field (name "POWER") "0.0625W")
        (field (name "AUTHOR") "CERN DEM JLC")
      )
      (libsource (lib "") (part "Resistor - 1%_1"))
    )
    (comp (ref "R180")
      (value "10k")
      (footprint "RESC1005X40N")
      (description "Resistor - 1%")
      (fields
        (field (name "PART NUMBER") "R0402_10K_1%_0.0625W_100PPM")
        (field (name "POWER") "0.0625W")
        (field (name "AUTHOR") "CERN DEM JLC")
      )
      (libsource (lib "") (part "Resistor - 1%_1"))
    )
    (comp (ref "R181")
      (value "13")
      (footprint "RESC1005X40N")
      (description "Resistor - 1%")
      (fields
        (field (name "TOLERANCE") "±1%")
        (field (name "PART NUMBER") "R0402_13R_1%_0.0625W_100PPM")
        (field (name "POWER") "0.0625W")
        (field (name "AUTHOR") "CERN DEM JLC")
      )
      (libsource (lib "") (part "Resistor - 1%_1"))
    )
    (comp (ref "R182")
      (value "1k")
      (footprint "RESC1005X40N")
      (description "Resistor - 1%")
      (fields
        (field (name "PART NUMBER") "R0402_1K_1%_0.0625W_100PPM")
        (field (name "POWER") "0.0625W")
        (field (name "AUTHOR") "CERN DEM JLC")
      )
      (libsource (lib "") (part "Resistor - 1%_1"))
    )
    (comp (ref "R183")
      (value "100")
      (footprint "RESC1005X40N")
      (description "Resistor - 1%")
      (fields
        (field (name "PART NUMBER") "R0402_100R_1%_0.0625W_100PPM")
        (field (name "POWER") "0.0625W")
        (field (name "AUTHOR") "CERN DEM JLC")
      )
      (libsource (lib "") (part "Resistor - 1%_1"))
    )
    (comp (ref "R184")
      (value "13")
      (footprint "RESC1005X40N")
      (description "Resistor - 1%")
      (fields
        (field (name "TOLERANCE") "±1%")
        (field (name "PART NUMBER") "R0402_13R_1%_0.0625W_100PPM")
        (field (name "POWER") "0.0625W")
        (field (name "AUTHOR") "CERN DEM JLC")
      )
      (libsource (lib "") (part "Resistor - 1%_1"))
    )
    (comp (ref "T15")
      (value "IRLML6402PBF")
      (footprint "SOT95P237X112-3N")
      (description "P-CHANNEL MOSFET WITH ZENER DIODE")
      (fields
        (field (name "MANUFACTURER") "INTERNATIONAL RECTIFIER")
        (field (name "MANUFACTURER PART NUMBER") "IRLML6402")
        (field (name "AUTHOR") "CERN DEM JLC")
      )
      (libsource (lib "ICs And Semiconductors") (part "P-MOSFET-DZ 1G 2S 3D"))
    )
    (comp (ref "T16")
      (value "IRLML0060TRPBF")
      (footprint "SOT95P237X112-3N")
      (description "N-CHANNEL MOSFET WITH DIODE")
      (fields
        (field (name "MANUFACTURER") "INTERNATIONAL RECTIFIER")
        (field (name "MANUFACTURER PART NUMBER") "IRLML0060")
        (field (name "AUTHOR") "CERN DEM JLC")
      )
      (libsource (lib "ICs And Semiconductors") (part "N-MOSFET-D 1G 2S 3D"))
    )
    (comp (ref "T17")
      (value "IRLML0060TRPBF")
      (footprint "SOT95P237X112-3N")
      (description "N-CHANNEL MOSFET WITH DIODE")
      (fields
        (field (name "MANUFACTURER") "INTERNATIONAL RECTIFIER")
        (field (name "MANUFACTURER PART NUMBER") "IRLML0060")
        (field (name "AUTHOR") "CERN DEM JLC")
      )
      (libsource (lib "ICs And Semiconductors") (part "N-MOSFET-D 1G 2S 3D"))
    )
  )
  (nets
    (net (code "1") (name "/ENBL") (class "Default")
      (node (ref "IC11") (pin "2") (pinfunction "IN_2") (pintype "input"))
      (node (ref "R172") (pin "2") (pinfunction "2_2") (pintype "passive"))
    )
    (net (code "2") (name "/ENBLn") (class "Default")
      (node (ref "IC11") (pin "1") (pinfunction "~{G}_1") (pintype "input"))
      (node (ref "R175") (pin "1") (pinfunction "1_1") (pintype "passive"))
    )
    (net (code "3") (name "/HV_AC") (class "Default")
      (node (ref "C73") (pin "1") (pinfunction "1_1") (pintype "passive"))
      (node (ref "L6") (pin "9") (pinfunction "9_9") (pintype "passive"))
    )
    (net (code "4") (name "/HV_OUT") (class "Default")
      (node (ref "R170") (pin "2") (pinfunction "2_2") (pintype "passive"))
      (node (ref "R76") (pin "2") (pinfunction "2_2") (pintype "passive"))
    )
    (net (code "5") (name "/I_CTRL") (class "Default")
      (node (ref "R93") (pin "2") (pinfunction "2_2") (pintype "passive"))
    )
    (net (code "6") (name "/I_MEAS") (class "Default")
      (node (ref "C134") (pin "2") (pinfunction "2_2") (pintype "passive"))
      (node (ref "R94") (pin "1") (pinfunction "1_1") (pintype "passive"))
    )
    (net (code "7") (name "/U_CTRL") (class "Default")
      (node (ref "R78") (pin "2") (pinfunction "2_2") (pintype "passive"))
    )
    (net (code "8") (name "/U_MEAS") (class "Default")
      (node (ref "C128") (pin "2") (pinfunction "2_2") (pintype "passive"))
      (node (ref "R80") (pin "1") (pinfunction "1_1") (pintype "passive"))
    )
    (net (code "9") (name "GNDp") (class "Default")
      (node (ref "C112") (pin "1") (pinfunction "1_1") (pintype "passive"))
      (node (ref "C113") (pin "1") (pinfunction "1_1") (pintype "passive"))
      (node (ref "C124") (pin "1") (pinfunction "1_1") (pintype "passive"))
      (node (ref "C125") (pin "1") (pinfunction "1_1") (pintype "passive"))
      (node (ref "C128") (pin "1") (pinfunction "1_1") (pintype "passive"))
      (node (ref "C129") (pin "1") (pinfunction "1_1") (pintype "passive"))
      (node (ref "C132") (pin "1") (pinfunction "1_1") (pintype "passive"))
      (node (ref "C133") (pin "1") (pinfunction "1_1") (pintype "passive"))
      (node (ref "C134") (pin "1") (pinfunction "1_1") (pintype "passive"))
      (node (ref "C16") (pin "1") (pinfunction "1_1") (pintype "passive"))
      (node (ref "C20") (pin "1") (pinfunction "1_1") (pintype "passive"))
      (node (ref "C21") (pin "1") (pinfunction "1_1") (pintype "passive"))
      (node (ref "C22") (pin "1") (pinfunction "1_1") (pintype "passive"))
      (node (ref "C69") (pin "1") (pinfunction "1_1") (pintype "passive"))
      (node (ref "C70") (pin "2") (pinfunction "2_2") (pintype "passive"))
      (node (ref "C71") (pin "1") (pinfunction "1_1") (pintype "passive"))
      (node (ref "C72") (pin "1") (pinfunction "1_1") (pintype "passive"))
      (node (ref "C74") (pin "2") (pinfunction "2_2") (pintype "passive"))
      (node (ref "C75") (pin "2") (pinfunction "2_2") (pintype "passive"))
      (node (ref "D18") (pin "1") (pinfunction "C_1") (pintype "passive"))
      (node (ref "D31") (pin "2") (pinfunction "A_2") (pintype "passive"))
      (node (ref "IC11") (pin "3") (pinfunction "GND_3") (pintype "power_in"))
      (node (ref "IC17") (pin "4") (pinfunction "V-_4") (pintype "passive"))
      (node (ref "IC9") (pin "15") (pinfunction "PGND_15") (pintype "power_in"))
      (node (ref "IC9") (pin "16") (pinfunction "GND_16") (pintype "power_in"))
      (node (ref "R173") (pin "2") (pinfunction "2_2") (pintype "passive"))
      (node (ref "R180") (pin "2") (pinfunction "2_2") (pintype "passive"))
      (node (ref "R184") (pin "1") (pinfunction "1_1") (pintype "passive"))
      (node (ref "R58") (pin "1") (pinfunction "1_1") (pintype "passive"))
      (node (ref "R60") (pin "2") (pinfunction "2_2") (pintype "passive"))
      (node (ref "R92") (pin "1") (pinfunction "1_1") (pintype "passive"))
      (node (ref "T16") (pin "2") (pinfunction "S_2") (pintype "passive"))
      (node (ref "T17") (pin "2") (pinfunction "S_2") (pintype "passive"))
    )
    (net (code "10") (name "N3V3p") (class "Default")
      (node (ref "C20") (pin "2") (pinfunction "2_2") (pintype "passive"))
      (node (ref "C21") (pin "2") (pinfunction "2_2") (pintype "passive"))
      (node (ref "C22") (pin "2") (pinfunction "2_2") (pintype "passive"))
      (node (ref "IC13") (pin "4") (pinfunction "V-_4") (pintype "power_in"))
      (node (ref "IC14") (pin "4") (pinfunction "V-_4") (pintype "power_in"))
      (node (ref "IC16") (pin "4") (pinfunction "V-_4") (pintype "power_in"))
    )
    (net (code "11") (name "Net-(C69-Pad2)") (class "Default")
      (node (ref "C69") (pin "2") (pinfunction "2_2") (pintype "passive"))
      (node (ref "L6") (pin "3") (pinfunction "3_3") (pintype "passive"))
      (node (ref "L8") (pin "2") (pinfunction "2_2") (pintype "passive"))
      (node (ref "R166") (pin "2") (pinfunction "2_2") (pintype "passive"))
    )
    (net (code "12") (name "Net-(C71-Pad2)") (class "Default")
      (node (ref "C71") (pin "2") (pinfunction "2_2") (pintype "passive"))
      (node (ref "R163") (pin "1") (pinfunction "1_1") (pintype "passive"))
    )
    (net (code "13") (name "Net-(C114-Pad1)") (class "Default")
      (node (ref "C114") (pin "1") (pinfunction "1_1") (pintype "passive"))
      (node (ref "C120") (pin "2") (pinfunction "2_2") (pintype "passive"))
    )
    (net (code "14") (name "Net-(C114-Pad2)") (class "Default")
      (node (ref "C114") (pin "2") (pinfunction "2_2") (pintype "passive"))
      (node (ref "R168") (pin "2") (pinfunction "2_2") (pintype "passive"))
      (node (ref "R169") (pin "1") (pinfunction "1_1") (pintype "passive"))
    )
    (net (code "15") (name "Net-(C115-Pad1)") (class "Default")
      (node (ref "C115") (pin "1") (pinfunction "1_1") (pintype "passive"))
      (node (ref "C121") (pin "2") (pinfunction "2_2") (pintype "passive"))
    )
    (net (code "16") (name "Net-(C115-Pad2)") (class "Default")
      (node (ref "C115") (pin "2") (pinfunction "2_2") (pintype "passive"))
      (node (ref "R169") (pin "2") (pinfunction "2_2") (pintype "passive"))
      (node (ref "R170") (pin "1") (pinfunction "1_1") (pintype "passive"))
    )
    (net (code "17") (name "Net-(C120-Pad1)") (class "Default")
      (node (ref "C120") (pin "1") (pinfunction "1_1") (pintype "passive"))
      (node (ref "C122") (pin "2") (pinfunction "2_2") (pintype "passive"))
    )
    (net (code "18") (name "Net-(C121-Pad1)") (class "Default")
      (node (ref "C121") (pin "1") (pinfunction "1_1") (pintype "passive"))
      (node (ref "C137") (pin "2") (pinfunction "2_2") (pintype "passive"))
    )
    (net (code "19") (name "Net-(C122-Pad1)") (class "Default")
      (node (ref "C122") (pin "1") (pinfunction "1_1") (pintype "passive"))
      (node (ref "C123") (pin "2") (pinfunction "2_2") (pintype "passive"))
    )
    (net (code "20") (name "Net-(C126-Pad2)") (class "Default")
      (node (ref "C126") (pin "2") (pinfunction "2_2") (pintype "passive"))
      (node (ref "R62") (pin "1") (pinfunction "1_1") (pintype "passive"))
    )
    (net (code "21") (name "Net-(C130-Pad2)") (class "Default")
      (node (ref "C130") (pin "2") (pinfunction "2_2") (pintype "passive"))
      (node (ref "R84") (pin "1") (pinfunction "1_1") (pintype "passive"))
    )
    (net (code "22") (name "Net-(C137-Pad1)") (class "Default")
      (node (ref "C137") (pin "1") (pinfunction "1_1") (pintype "passive"))
      (node (ref "C138") (pin "2") (pinfunction "2_2") (pintype "passive"))
    )
    (net (code "23") (name "Net-(D1-A)") (class "Default")
      (node (ref "C109") (pin "1") (pinfunction "1_1") (pintype "passive"))
      (node (ref "C73") (pin "2") (pinfunction "2_2") (pintype "passive"))
      (node (ref "D1") (pin "2") (pinfunction "A_2") (pintype "passive"))
      (node (ref "D32") (pin "2") (pinfunction "A_2") (pintype "passive"))
      (node (ref "D33") (pin "1") (pinfunction "C_1") (pintype "passive"))
      (node (ref "D39") (pin "1") (pinfunction "C_1") (pintype "passive"))
    )
    (net (code "24") (name "Net-(D1-C)") (class "Default")
      (node (ref "C116") (pin "1") (pinfunction "1_1") (pintype "passive"))
      (node (ref "C123") (pin "1") (pinfunction "1_1") (pintype "passive"))
      (node (ref "C132") (pin "2") (pinfunction "2_2") (pintype "passive"))
      (node (ref "C138") (pin "1") (pinfunction "1_1") (pintype "passive"))
      (node (ref "D1") (pin "1") (pinfunction "C_1") (pintype "passive"))
      (node (ref "D16") (pin "1") (pinfunction "C_1") (pintype "passive"))
      (node (ref "D39") (pin "2") (pinfunction "A_2") (pintype "passive"))
      (node (ref "L6") (pin "8") (pinfunction "8_8") (pintype "passive"))
      (node (ref "R183") (pin "2") (pinfunction "2_2") (pintype "passive"))
      (node (ref "R89") (pin "2") (pinfunction "2_2") (pintype "passive"))
    )
    (net (code "25") (name "Net-(D14-A)") (class "Default")
      (node (ref "D14") (pin "2") (pinfunction "A_2") (pintype "passive"))
      (node (ref "IC17") (pin "2") (pinfunction "IN-_2") (pintype "passive"))
      (node (ref "R176") (pin "2") (pinfunction "2_2") (pintype "passive"))
      (node (ref "R178") (pin "1") (pinfunction "1_1") (pintype "passive"))
    )
    (net (code "26") (name "Net-(D14-C)") (class "Default")
      (node (ref "D14") (pin "1") (pinfunction "C_1") (pintype "passive"))
      (node (ref "IC17") (pin "1") (pinfunction "OUT_1") (pintype "passive"))
      (node (ref "R176") (pin "1") (pinfunction "1_1") (pintype "passive"))
      (node (ref "R49") (pin "1") (pinfunction "1_1") (pintype "passive"))
    )
    (net (code "27") (name "Net-(D15-A)") (class "Default")
      (node (ref "D15") (pin "2") (pinfunction "A_2") (pintype "passive"))
      (node (ref "D17") (pin "2") (pinfunction "A_2") (pintype "passive"))
      (node (ref "R177") (pin "2") (pinfunction "2_2") (pintype "passive"))
      (node (ref "R178") (pin "2") (pinfunction "2_2") (pintype "passive"))
    )
    (net (code "28") (name "Net-(D15-C)") (class "Default")
      (node (ref "C126") (pin "1") (pinfunction "1_1") (pintype "passive"))
      (node (ref "C127") (pin "1") (pinfunction "1_1") (pintype "passive"))
      (node (ref "D15") (pin "1") (pinfunction "C_1") (pintype "passive"))
      (node (ref "IC16") (pin "1") (pinfunction "OUT_1") (pintype "output"))
    )
    (net (code "29") (name "Net-(D16-A)") (class "Default")
      (node (ref "D16") (pin "2") (pinfunction "A_2") (pintype "passive"))
      (node (ref "D18") (pin "2") (pinfunction "A_2") (pintype "passive"))
    )
    (net (code "30") (name "Net-(D17-C)") (class "Default")
      (node (ref "C130") (pin "1") (pinfunction "1_1") (pintype "passive"))
      (node (ref "C131") (pin "1") (pinfunction "1_1") (pintype "passive"))
      (node (ref "D17") (pin "1") (pinfunction "C_1") (pintype "passive"))
      (node (ref "IC16") (pin "7") (pinfunction "OUT_7") (pintype "output"))
    )
    (net (code "31") (name "Net-(D19-A)") (class "Default")
      (node (ref "C116") (pin "2") (pinfunction "2_2") (pintype "passive"))
      (node (ref "C117") (pin "1") (pinfunction "1_1") (pintype "passive"))
      (node (ref "D19") (pin "2") (pinfunction "A_2") (pintype "passive"))
      (node (ref "D25") (pin "1") (pinfunction "C_1") (pintype "passive"))
      (node (ref "D32") (pin "1") (pinfunction "C_1") (pintype "passive"))
      (node (ref "D33") (pin "2") (pinfunction "A_2") (pintype "passive"))
    )
    (net (code "32") (name "Net-(D19-C)") (class "Default")
      (node (ref "C109") (pin "2") (pinfunction "2_2") (pintype "passive"))
      (node (ref "C110") (pin "1") (pinfunction "1_1") (pintype "passive"))
      (node (ref "D19") (pin "1") (pinfunction "C_1") (pintype "passive"))
      (node (ref "D20") (pin "2") (pinfunction "A_2") (pintype "passive"))
      (node (ref "D25") (pin "2") (pinfunction "A_2") (pintype "passive"))
      (node (ref "D26") (pin "1") (pinfunction "C_1") (pintype "passive"))
    )
    (net (code "33") (name "Net-(D20-C)") (class "Default")
      (node (ref "C117") (pin "2") (pinfunction "2_2") (pintype "passive"))
      (node (ref "C118") (pin "1") (pinfunction "1_1") (pintype "passive"))
      (node (ref "D20") (pin "1") (pinfunction "C_1") (pintype "passive"))
      (node (ref "D21") (pin "2") (pinfunction "A_2") (pintype "passive"))
      (node (ref "D26") (pin "2") (pinfunction "A_2") (pintype "passive"))
      (node (ref "D27") (pin "1") (pinfunction "C_1") (pintype "passive"))
    )
    (net (code "34") (name "Net-(D21-C)") (class "Default")
      (node (ref "C110") (pin "2") (pinfunction "2_2") (pintype "passive"))
      (node (ref "C111") (pin "1") (pinfunction "1_1") (pintype "passive"))
      (node (ref "D21") (pin "1") (pinfunction "C_1") (pintype "passive"))
      (node (ref "D22") (pin "2") (pinfunction "A_2") (pintype "passive"))
      (node (ref "D27") (pin "2") (pinfunction "A_2") (pintype "passive"))
      (node (ref "D28") (pin "1") (pinfunction "C_1") (pintype "passive"))
    )
    (net (code "35") (name "Net-(D22-C)") (class "Default")
      (node (ref "C118") (pin "2") (pinfunction "2_2") (pintype "passive"))
      (node (ref "C119") (pin "1") (pinfunction "1_1") (pintype "passive"))
      (node (ref "D22") (pin "1") (pinfunction "C_1") (pintype "passive"))
      (node (ref "D23") (pin "2") (pinfunction "A_2") (pintype "passive"))
      (node (ref "D28") (pin "2") (pinfunction "A_2") (pintype "passive"))
      (node (ref "D29") (pin "1") (pinfunction "C_1") (pintype "passive"))
    )
    (net (code "36") (name "Net-(D23-C)") (class "Default")
      (node (ref "C111") (pin "2") (pinfunction "2_2") (pintype "passive"))
      (node (ref "D23") (pin "1") (pinfunction "C_1") (pintype "passive"))
      (node (ref "D24") (pin "2") (pinfunction "A_2") (pintype "passive"))
      (node (ref "D29") (pin "2") (pinfunction "A_2") (pintype "passive"))
      (node (ref "D30") (pin "1") (pinfunction "C_1") (pintype "passive"))
    )
    (net (code "37") (name "Net-(D24-C)") (class "Default")
      (node (ref "C119") (pin "2") (pinfunction "2_2") (pintype "passive"))
      (node (ref "D24") (pin "1") (pinfunction "C_1") (pintype "passive"))
      (node (ref "D30") (pin "2") (pinfunction "A_2") (pintype "passive"))
      (node (ref "R168") (pin "1") (pinfunction "1_1") (pintype "passive"))
    )
    (net (code "38") (name "Net-(D31-C)") (class "Default")
      (node (ref "D31") (pin "1") (pinfunction "C_1") (pintype "passive"))
      (node (ref "L8") (pin "1") (pinfunction "1_1") (pintype "passive"))
      (node (ref "T15") (pin "3") (pinfunction "D_3") (pintype "passive"))
    )
    (net (code "39") (name "Net-(IC9-AOUT)") (class "Default")
      (node (ref "IC9") (pin "2") (pinfunction "AOUT_2") (pintype "output"))
      (node (ref "R167") (pin "1") (pinfunction "1_1") (pintype "passive"))
    )
    (net (code "40") (name "Net-(IC9-BOUT)") (class "Default")
      (node (ref "IC9") (pin "1") (pinfunction "BOUT_1") (pintype "output"))
      (node (ref "R171") (pin "1") (pinfunction "1_1") (pintype "passive"))
    )
    (net (code "41") (name "Net-(IC9-COMP)") (class "Default")
      (node (ref "IC9") (pin "4") (pinfunction "COMP_4") (pintype "output"))
      (node (ref "R174") (pin "1") (pinfunction "1_1") (pintype "passive"))
    )
    (net (code "42") (name "Net-(IC9-COUT)") (class "Default")
      (node (ref "IC9") (pin "14") (pinfunction "COUT_14") (pintype "output"))
      (node (ref "R165") (pin "1") (pinfunction "1_1") (pintype "passive"))
    )
    (net (code "43") (name "Net-(IC9-CT)") (class "Default")
      (node (ref "C74") (pin "1") (pinfunction "1_1") (pintype "passive"))
      (node (ref "IC9") (pin "8") (pinfunction "CT_8") (pintype "passive"))
    )
    (net (code "44") (name "Net-(IC9-ENBL)") (class "Default")
      (node (ref "IC9") (pin "13") (pinfunction "ENBL_13") (pintype "input"))
      (node (ref "R172") (pin "1") (pinfunction "1_1") (pintype "passive"))
      (node (ref "R173") (pin "1") (pinfunction "1_1") (pintype "passive"))
    )
    (net (code "45") (name "Net-(IC9-INV)") (class "Default")
      (node (ref "IC9") (pin "7") (pinfunction "INV_7") (pintype "input"))
      (node (ref "R174") (pin "2") (pinfunction "2_2") (pintype "passive"))
      (node (ref "R49") (pin "2") (pinfunction "2_2") (pintype "passive"))
    )
    (net (code "46") (name "Net-(IC9-REF)") (class "Default")
      (node (ref "C112") (pin "2") (pinfunction "2_2") (pintype "passive"))
      (node (ref "IC9") (pin "11") (pinfunction "REF_11") (pintype "output"))
      (node (ref "R179") (pin "2") (pinfunction "2_2") (pintype "passive"))
    )
    (net (code "47") (name "Net-(IC9-SS)") (class "Default")
      (node (ref "C113") (pin "2") (pinfunction "2_2") (pintype "passive"))
      (node (ref "IC9") (pin "5") (pinfunction "SS_5") (pintype "passive"))
    )
    (net (code "48") (name "Net-(IC9-VC)") (class "Default")
      (node (ref "C72") (pin "2") (pinfunction "2_2") (pintype "passive"))
      (node (ref "C75") (pin "1") (pinfunction "1_1") (pintype "passive"))
      (node (ref "IC9") (pin "12") (pinfunction "VCC_12") (pintype "power_in"))
      (node (ref "IC9") (pin "3") (pinfunction "VC_3") (pintype "power_in"))
      (node (ref "R164") (pin "2") (pinfunction "2_2") (pintype "passive"))
    )
    (net (code "49") (name "Net-(IC9-ZD)") (class "Default")
      (node (ref "IC9") (pin "9") (pinfunction "ZD_9") (pintype "input"))
      (node (ref "R166") (pin "1") (pinfunction "1_1") (pintype "passive"))
    )
    (net (code "50") (name "Net-(IC11-OUT)") (class "Default")
      (node (ref "IC11") (pin "4") (pinfunction "OUT_4") (pintype "tri_state"))
      (node (ref "R177") (pin "1") (pinfunction "1_1") (pintype "passive"))
    )
    (net (code "51") (name "Net-(IC13A-IN+)") (class "Default")
      (node (ref "IC13") (pin "3") (pinfunction "IN+_3") (pintype "input"))
      (node (ref "R28") (pin "2") (pinfunction "2_2") (pintype "passive"))
      (node (ref "R74") (pin "1") (pinfunction "1_1") (pintype "passive"))
    )
    (net (code "52") (name "Net-(IC13A-IN-)") (class "Default")
      (node (ref "IC13") (pin "2") (pinfunction "IN-_2") (pintype "input"))
      (node (ref "R181") (pin "2") (pinfunction "2_2") (pintype "passive"))
      (node (ref "R63") (pin "1") (pinfunction "1_1") (pintype "passive"))
    )
    (net (code "53") (name "Net-(IC13A-OUT)") (class "Default")
      (node (ref "IC13") (pin "1") (pinfunction "OUT_1") (pintype "output"))
      (node (ref "R73") (pin "2") (pinfunction "2_2") (pintype "passive"))
      (node (ref "R85") (pin "2") (pinfunction "2_2") (pintype "passive"))
      (node (ref "R9") (pin "1") (pinfunction "1_1") (pintype "passive"))
    )
    (net (code "54") (name "Net-(IC13B-IN+)") (class "Default")
      (node (ref "IC13") (pin "5") (pinfunction "IN+_5") (pintype "input"))
      (node (ref "R73") (pin "1") (pinfunction "1_1") (pintype "passive"))
    )
    (net (code "55") (name "Net-(IC13B-IN-)") (class "Default")
      (node (ref "IC13") (pin "6") (pinfunction "IN-_6") (pintype "input"))
      (node (ref "R60") (pin "1") (pinfunction "1_1") (pintype "passive"))
      (node (ref "R61") (pin "2") (pinfunction "2_2") (pintype "passive"))
    )
    (net (code "56") (name "Net-(IC13B-OUT)") (class "Default")
      (node (ref "IC13") (pin "7") (pinfunction "OUT_7") (pintype "output"))
      (node (ref "R182") (pin "2") (pinfunction "2_2") (pintype "passive"))
      (node (ref "R61") (pin "1") (pinfunction "1_1") (pintype "passive"))
      (node (ref "R80") (pin "2") (pinfunction "2_2") (pintype "passive"))
    )
    (net (code "57") (name "Net-(IC14A-IN+)") (class "Default")
      (node (ref "IC14") (pin "3") (pinfunction "IN+_3") (pintype "input"))
      (node (ref "R89") (pin "1") (pinfunction "1_1") (pintype "passive"))
      (node (ref "R91") (pin "2") (pinfunction "2_2") (pintype "passive"))
    )
    (net (code "58") (name "Net-(IC14A-IN-)") (class "Default")
      (node (ref "IC14") (pin "2") (pinfunction "IN-_2") (pintype "input"))
      (node (ref "R183") (pin "1") (pinfunction "1_1") (pintype "passive"))
      (node (ref "R82") (pin "2") (pinfunction "2_2") (pintype "passive"))
    )
    (net (code "59") (name "Net-(IC14A-OUT)") (class "Default")
      (node (ref "IC14") (pin "1") (pinfunction "OUT_1") (pintype "output"))
      (node (ref "R79") (pin "1") (pinfunction "1_1") (pintype "passive"))
      (node (ref "R87") (pin "2") (pinfunction "2_2") (pintype "passive"))
    )
    (net (code "60") (name "Net-(IC14B-IN+)") (class "Default")
      (node (ref "IC14") (pin "5") (pinfunction "IN+_5") (pintype "input"))
      (node (ref "R87") (pin "1") (pinfunction "1_1") (pintype "passive"))
      (node (ref "R88") (pin "2") (pinfunction "2_2") (pintype "passive"))
    )
    (net (code "61") (name "Net-(IC14B-IN-)") (class "Default")
      (node (ref "IC14") (pin "6") (pinfunction "IN-_6") (pintype "input"))
      (node (ref "R85") (pin "1") (pinfunction "1_1") (pintype "passive"))
      (node (ref "R86") (pin "2") (pinfunction "2_2") (pintype "passive"))
    )
    (net (code "62") (name "Net-(IC14B-OUT)") (class "Default")
      (node (ref "IC14") (pin "7") (pinfunction "OUT_7") (pintype "output"))
      (node (ref "R83") (pin "1") (pinfunction "1_1") (pintype "passive"))
      (node (ref "R90") (pin "2") (pinfunction "2_2") (pintype "passive"))
      (node (ref "R94") (pin "2") (pinfunction "2_2") (pintype "passive"))
    )
    (net (code "63") (name "Net-(IC16A-IN+)") (class "Default")
      (node (ref "IC16") (pin "3") (pinfunction "IN+_3") (pintype "input"))
      (node (ref "R78") (pin "1") (pinfunction "1_1") (pintype "passive"))
    )
    (net (code "64") (name "Net-(IC16A-IN-)") (class "Default")
      (node (ref "C127") (pin "2") (pinfunction "2_2") (pintype "passive"))
      (node (ref "IC16") (pin "2") (pinfunction "IN-_2") (pintype "input"))
      (node (ref "R182") (pin "1") (pinfunction "1_1") (pintype "passive"))
      (node (ref "R62") (pin "2") (pinfunction "2_2") (pintype "passive"))
    )
    (net (code "65") (name "Net-(IC16B-IN+)") (class "Default")
      (node (ref "IC16") (pin "5") (pinfunction "IN+_5") (pintype "input"))
      (node (ref "R93") (pin "1") (pinfunction "1_1") (pintype "passive"))
    )
    (net (code "66") (name "Net-(IC16B-IN-)") (class "Default")
      (node (ref "C131") (pin "2") (pinfunction "2_2") (pintype "passive"))
      (node (ref "IC16") (pin "6") (pinfunction "IN-_6") (pintype "input"))
      (node (ref "R84") (pin "2") (pinfunction "2_2") (pintype "passive"))
      (node (ref "R90") (pin "1") (pinfunction "1_1") (pintype "passive"))
    )
    (net (code "67") (name "Net-(IC17A-IN+)") (class "Default")
      (node (ref "IC17") (pin "3") (pinfunction "IN+_3") (pintype "passive"))
      (node (ref "R179") (pin "1") (pinfunction "1_1") (pintype "passive"))
      (node (ref "R180") (pin "1") (pinfunction "1_1") (pintype "passive"))
    )
    (net (code "68") (name "Net-(R28-Pad1)") (class "Default")
      (node (ref "R28") (pin "1") (pinfunction "1_1") (pintype "passive"))
      (node (ref "R58") (pin "2") (pinfunction "2_2") (pintype "passive"))
    )
    (net (code "69") (name "Net-(R63-Pad2)") (class "Default")
      (node (ref "R63") (pin "2") (pinfunction "2_2") (pintype "passive"))
      (node (ref "R74") (pin "2") (pinfunction "2_2") (pintype "passive"))
      (node (ref "R81") (pin "1") (pinfunction "1_1") (pintype "passive"))
    )
    (net (code "70") (name "Net-(R75-Pad1)") (class "Default")
      (node (ref "R75") (pin "1") (pinfunction "1_1") (pintype "passive"))
      (node (ref "R77") (pin "2") (pinfunction "2_2") (pintype "passive"))
    )
    (net (code "71") (name "Net-(R75-Pad2)") (class "Default")
      (node (ref "R75") (pin "2") (pinfunction "2_2") (pintype "passive"))
      (node (ref "R76") (pin "1") (pinfunction "1_1") (pintype "passive"))
    )
    (net (code "72") (name "Net-(R77-Pad1)") (class "Default")
      (node (ref "R77") (pin "1") (pinfunction "1_1") (pintype "passive"))
      (node (ref "R81") (pin "2") (pinfunction "2_2") (pintype "passive"))
    )
    (net (code "73") (name "Net-(R79-Pad2)") (class "Default")
      (node (ref "R79") (pin "2") (pinfunction "2_2") (pintype "passive"))
      (node (ref "R82") (pin "1") (pinfunction "1_1") (pintype "passive"))
    )
    (net (code "74") (name "Net-(R83-Pad2)") (class "Default")
      (node (ref "R83") (pin "2") (pinfunction "2_2") (pintype "passive"))
      (node (ref "R86") (pin "1") (pinfunction "1_1") (pintype "passive"))
    )
    (net (code "75") (name "Net-(R88-Pad1)") (class "Default")
      (node (ref "R88") (pin "1") (pinfunction "1_1") (pintype "passive"))
      (node (ref "R92") (pin "2") (pinfunction "2_2") (pintype "passive"))
    )
    (net (code "76") (name "Net-(R181-Pad1)") (class "Default")
      (node (ref "R181") (pin "1") (pinfunction "1_1") (pintype "passive"))
      (node (ref "R9") (pin "2") (pinfunction "2_2") (pintype "passive"))
    )
    (net (code "77") (name "Net-(R184-Pad2)") (class "Default")
      (node (ref "R184") (pin "2") (pinfunction "2_2") (pintype "passive"))
      (node (ref "R91") (pin "1") (pinfunction "1_1") (pintype "passive"))
    )
    (net (code "78") (name "Net-(T15-G)") (class "Default")
      (node (ref "R165") (pin "2") (pinfunction "2_2") (pintype "passive"))
      (node (ref "T15") (pin "1") (pinfunction "G_1") (pintype "passive"))
    )
    (net (code "79") (name "Net-(T16-D)") (class "Default")
      (node (ref "C76") (pin "2") (pinfunction "2_2") (pintype "passive"))
      (node (ref "L6") (pin "5") (pinfunction "5_5") (pintype "passive"))
      (node (ref "T16") (pin "3") (pinfunction "D_3") (pintype "passive"))
    )
    (net (code "80") (name "Net-(T16-G)") (class "Default")
      (node (ref "R167") (pin "2") (pinfunction "2_2") (pintype "passive"))
      (node (ref "T16") (pin "1") (pinfunction "G_1") (pintype "passive"))
    )
    (net (code "81") (name "Net-(T17-D)") (class "Default")
      (node (ref "C76") (pin "1") (pinfunction "1_1") (pintype "passive"))
      (node (ref "L6") (pin "1") (pinfunction "1_1") (pintype "passive"))
      (node (ref "T17") (pin "3") (pinfunction "D_3") (pintype "passive"))
    )
    (net (code "82") (name "Net-(T17-G)") (class "Default")
      (node (ref "R171") (pin "2") (pinfunction "2_2") (pintype "passive"))
      (node (ref "T17") (pin "1") (pinfunction "G_1") (pintype "passive"))
    )
    (net (code "83") (name "P3V3Ap") (class "Default")
      (node (ref "R175") (pin "2") (pinfunction "2_2") (pintype "passive"))
    )
    (net (code "84") (name "P5V0Ap") (class "Default")
      (node (ref "C124") (pin "2") (pinfunction "2_2") (pintype "passive"))
      (node (ref "C125") (pin "2") (pinfunction "2_2") (pintype "passive"))
      (node (ref "C129") (pin "2") (pinfunction "2_2") (pintype "passive"))
      (node (ref "C133") (pin "2") (pinfunction "2_2") (pintype "passive"))
      (node (ref "C16") (pin "2") (pinfunction "2_2") (pintype "passive"))
      (node (ref "IC11") (pin "5") (pinfunction "VCC_5") (pintype "power_in"))
      (node (ref "IC13") (pin "8") (pinfunction "V+_8") (pintype "power_in"))
      (node (ref "IC14") (pin "8") (pinfunction "V+_8") (pintype "power_in"))
      (node (ref "IC16") (pin "8") (pinfunction "V+_8") (pintype "power_in"))
      (node (ref "IC17") (pin "8") (pinfunction "V+_8") (pintype "passive"))
    )
    (net (code "85") (name "P12V0p") (class "Default")
      (node (ref "C70") (pin "1") (pinfunction "1_1") (pintype "passive"))
      (node (ref "R163") (pin "2") (pinfunction "2_2") (pintype "passive"))
      (node (ref "R164") (pin "1") (pinfunction "1_1") (pintype "passive"))
      (node (ref "T15") (pin "2") (pinfunction "S_2") (pintype "passive"))
    )
    (net (code "86") (name "unconnected-(IC9-nc-Pad6)") (class "Default")
      (node (ref "IC9") (pin "6") (pinfunction "nc_6") (pintype "passive"))
    )
    (net (code "87") (name "unconnected-(IC9-nc-Pad10)") (class "Default")
      (node (ref "IC9") (pin "10") (pinfunction "nc_10") (pintype "passive"))
    )
    (net (code "88") (name "unconnected-(L6-Pad2)") (class "Default")
      (node (ref "L6") (pin "2") (pinfunction "2_2") (pintype "passive"))
    )
    (net (code "89") (name "unconnected-(L6-Pad4)") (class "Default")
      (node (ref "L6") (pin "4") (pinfunction "4_4") (pintype "passive"))
    )
  )
)
